# BACK-LIGHT-II.net
KiCad netlist of a schematic drawn in Altium Designer
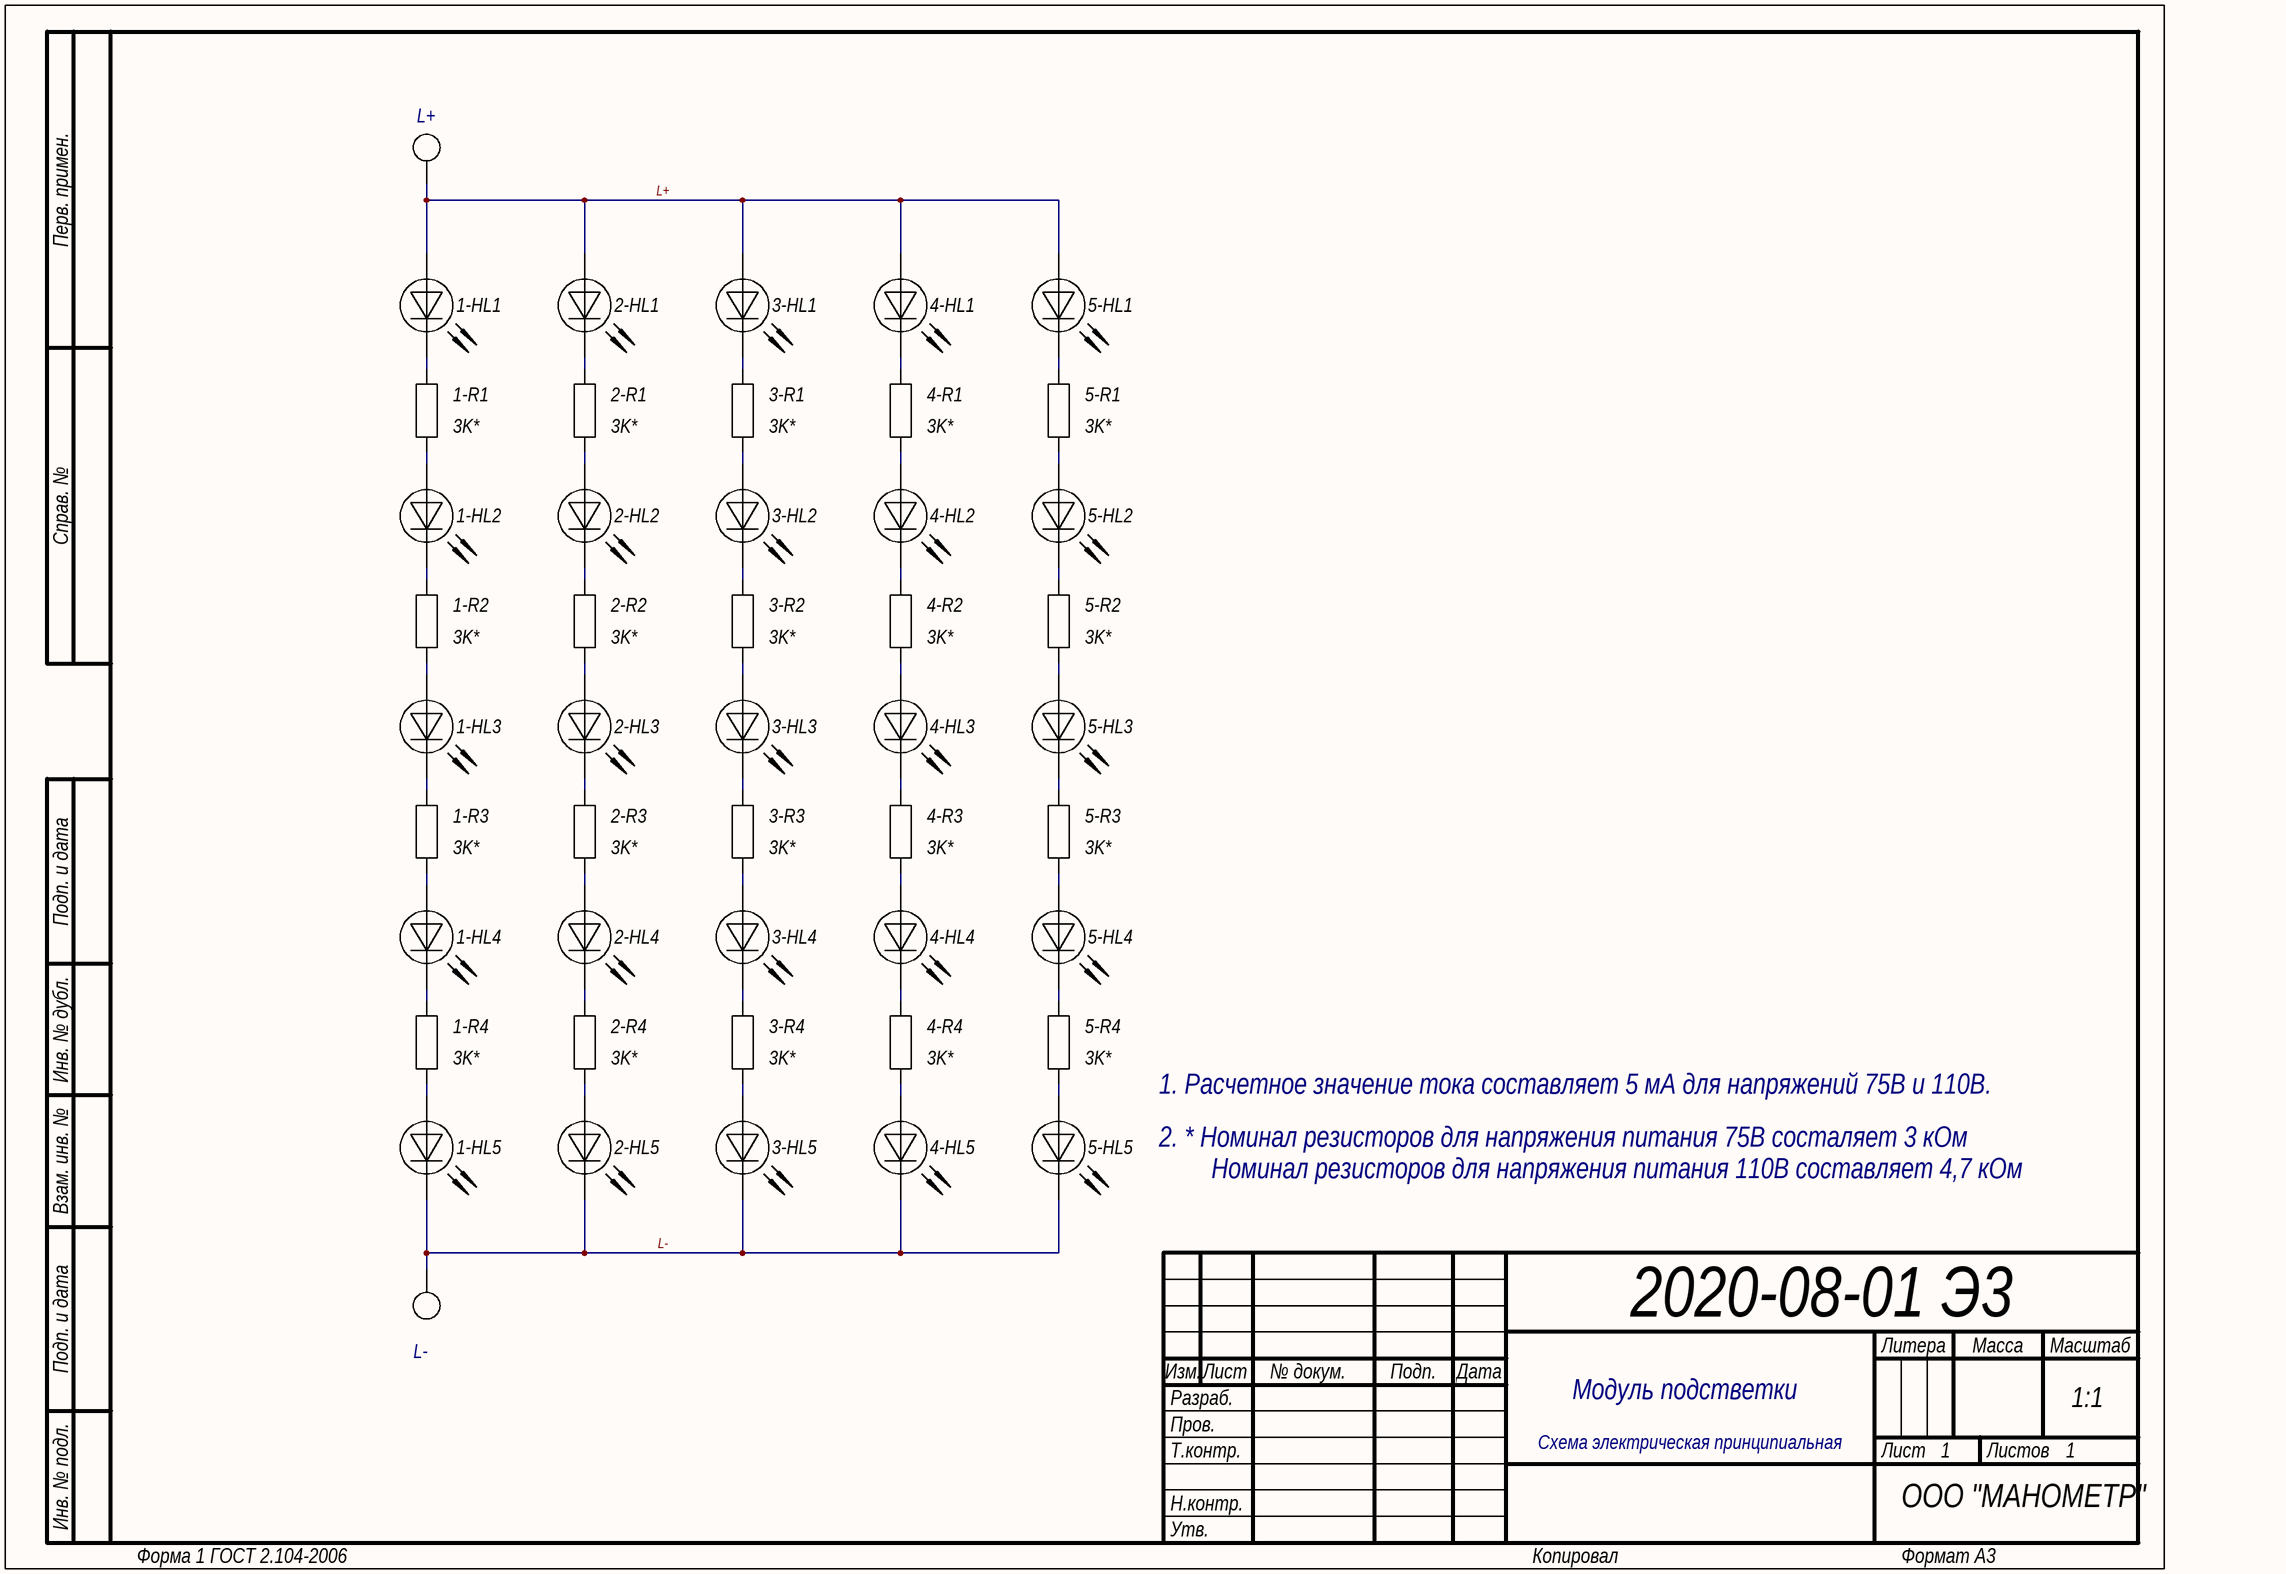
[diagram p0: BACK-LIGHT-II.SchDoc]

(export (version "E")
  (design (tool "Eeschema 10.0.6"))
  (components
    (comp (ref "1-HL1")
      (value "FYLS-1206UWC")
      (footprint "LED 1206")
      (description "Светодиод")
      (fields (field (name "TOLERANCE") "3K*"))
      (libsource (lib "MAXX") (part "LED"))
    )
    (comp (ref "1-HL2")
      (value "FYLS-1206UWC")
      (footprint "LED 1206")
      (description "Светодиод")
      (fields (field (name "TOLERANCE") "3K*"))
      (libsource (lib "MAXX") (part "LED"))
    )
    (comp (ref "1-HL3")
      (value "FYLS-1206UWC")
      (footprint "LED 1206")
      (description "Светодиод")
      (fields (field (name "TOLERANCE") "3K*"))
      (libsource (lib "MAXX") (part "LED"))
    )
    (comp (ref "1-HL4")
      (value "FYLS-1206UWC")
      (footprint "LED 1206")
      (description "Светодиод")
      (fields (field (name "TOLERANCE") "3K*"))
      (libsource (lib "MAXX") (part "LED"))
    )
    (comp (ref "1-HL5")
      (value "FYLS-1206UWC")
      (footprint "LED 1206")
      (description "Светодиод")
      (fields (field (name "TOLERANCE") "3K*"))
      (libsource (lib "MAXX") (part "LED"))
    )
    (comp (ref "1-R1")
      (value "3K*")
      (footprint "RC1206")
      (description "Постоянный углеродистый резистор")
      (libsource (lib "MAXX") (part "RES"))
    )
    (comp (ref "1-R2")
      (value "3K*")
      (footprint "RC1206")
      (description "Постоянный углеродистый резистор")
      (libsource (lib "MAXX") (part "RES"))
    )
    (comp (ref "1-R3")
      (value "3K*")
      (footprint "RC1206")
      (description "Постоянный углеродистый резистор")
      (libsource (lib "MAXX") (part "RES"))
    )
    (comp (ref "1-R4")
      (value "3K*")
      (footprint "RC1206")
      (description "Постоянный углеродистый резистор")
      (libsource (lib "MAXX") (part "RES"))
    )
    (comp (ref "2-HL1")
      (value "FYLS-1206UWC")
      (footprint "LED 1206")
      (description "Светодиод")
      (fields (field (name "TOLERANCE") "3K*"))
      (libsource (lib "MAXX") (part "LED"))
    )
    (comp (ref "2-HL2")
      (value "FYLS-1206UWC")
      (footprint "LED 1206")
      (description "Светодиод")
      (fields (field (name "TOLERANCE") "3K*"))
      (libsource (lib "MAXX") (part "LED"))
    )
    (comp (ref "2-HL3")
      (value "FYLS-1206UWC")
      (footprint "LED 1206")
      (description "Светодиод")
      (fields (field (name "TOLERANCE") "3K*"))
      (libsource (lib "MAXX") (part "LED"))
    )
    (comp (ref "2-HL4")
      (value "FYLS-1206UWC")
      (footprint "LED 1206")
      (description "Светодиод")
      (fields (field (name "TOLERANCE") "3K*"))
      (libsource (lib "MAXX") (part "LED"))
    )
    (comp (ref "2-HL5")
      (value "FYLS-1206UWC")
      (footprint "LED 1206")
      (description "Светодиод")
      (fields (field (name "TOLERANCE") "3K*"))
      (libsource (lib "MAXX") (part "LED"))
    )
    (comp (ref "2-R1")
      (value "3K*")
      (footprint "RC1206")
      (description "Постоянный углеродистый резистор")
      (libsource (lib "MAXX") (part "RES"))
    )
    (comp (ref "2-R2")
      (value "3K*")
      (footprint "RC1206")
      (description "Постоянный углеродистый резистор")
      (libsource (lib "MAXX") (part "RES"))
    )
    (comp (ref "2-R3")
      (value "3K*")
      (footprint "RC1206")
      (description "Постоянный углеродистый резистор")
      (libsource (lib "MAXX") (part "RES"))
    )
    (comp (ref "2-R4")
      (value "3K*")
      (footprint "RC1206")
      (description "Постоянный углеродистый резистор")
      (libsource (lib "MAXX") (part "RES"))
    )
    (comp (ref "3-HL1")
      (value "FYLS-1206UWC")
      (footprint "LED 1206")
      (description "Светодиод")
      (fields (field (name "TOLERANCE") "3K*"))
      (libsource (lib "MAXX") (part "LED"))
    )
    (comp (ref "3-HL2")
      (value "FYLS-1206UWC")
      (footprint "LED 1206")
      (description "Светодиод")
      (fields (field (name "TOLERANCE") "3K*"))
      (libsource (lib "MAXX") (part "LED"))
    )
    (comp (ref "3-HL3")
      (value "FYLS-1206UWC")
      (footprint "LED 1206")
      (description "Светодиод")
      (fields (field (name "TOLERANCE") "3K*"))
      (libsource (lib "MAXX") (part "LED"))
    )
    (comp (ref "3-HL4")
      (value "FYLS-1206UWC")
      (footprint "LED 1206")
      (description "Светодиод")
      (fields (field (name "TOLERANCE") "3K*"))
      (libsource (lib "MAXX") (part "LED"))
    )
    (comp (ref "3-HL5")
      (value "FYLS-1206UWC")
      (footprint "LED 1206")
      (description "Светодиод")
      (fields (field (name "TOLERANCE") "3K*"))
      (libsource (lib "MAXX") (part "LED"))
    )
    (comp (ref "3-R1")
      (value "3K*")
      (footprint "RC1206")
      (description "Постоянный углеродистый резистор")
      (libsource (lib "MAXX") (part "RES"))
    )
    (comp (ref "3-R2")
      (value "3K*")
      (footprint "RC1206")
      (description "Постоянный углеродистый резистор")
      (libsource (lib "MAXX") (part "RES"))
    )
    (comp (ref "3-R3")
      (value "3K*")
      (footprint "RC1206")
      (description "Постоянный углеродистый резистор")
      (libsource (lib "MAXX") (part "RES"))
    )
    (comp (ref "3-R4")
      (value "3K*")
      (footprint "RC1206")
      (description "Постоянный углеродистый резистор")
      (libsource (lib "MAXX") (part "RES"))
    )
    (comp (ref "4-HL1")
      (value "FYLS-1206UWC")
      (footprint "LED 1206")
      (description "Светодиод")
      (fields (field (name "TOLERANCE") "3K*"))
      (libsource (lib "MAXX") (part "LED"))
    )
    (comp (ref "4-HL2")
      (value "FYLS-1206UWC")
      (footprint "LED 1206")
      (description "Светодиод")
      (fields (field (name "TOLERANCE") "3K*"))
      (libsource (lib "MAXX") (part "LED"))
    )
    (comp (ref "4-HL3")
      (value "FYLS-1206UWC")
      (footprint "LED 1206")
      (description "Светодиод")
      (fields (field (name "TOLERANCE") "3K*"))
      (libsource (lib "MAXX") (part "LED"))
    )
    (comp (ref "4-HL4")
      (value "FYLS-1206UWC")
      (footprint "LED 1206")
      (description "Светодиод")
      (fields (field (name "TOLERANCE") "3K*"))
      (libsource (lib "MAXX") (part "LED"))
    )
    (comp (ref "4-HL5")
      (value "FYLS-1206UWC")
      (footprint "LED 1206")
      (description "Светодиод")
      (fields (field (name "TOLERANCE") "3K*"))
      (libsource (lib "MAXX") (part "LED"))
    )
    (comp (ref "4-R1")
      (value "3K*")
      (footprint "RC1206")
      (description "Постоянный углеродистый резистор")
      (libsource (lib "MAXX") (part "RES"))
    )
    (comp (ref "4-R2")
      (value "3K*")
      (footprint "RC1206")
      (description "Постоянный углеродистый резистор")
      (libsource (lib "MAXX") (part "RES"))
    )
    (comp (ref "4-R3")
      (value "3K*")
      (footprint "RC1206")
      (description "Постоянный углеродистый резистор")
      (libsource (lib "MAXX") (part "RES"))
    )
    (comp (ref "4-R4")
      (value "3K*")
      (footprint "RC1206")
      (description "Постоянный углеродистый резистор")
      (libsource (lib "MAXX") (part "RES"))
    )
    (comp (ref "5-HL1")
      (value "FYLS-1206UWC")
      (footprint "LED 1206")
      (description "Светодиод")
      (fields (field (name "TOLERANCE") "3K*"))
      (libsource (lib "MAXX") (part "LED"))
    )
    (comp (ref "5-HL2")
      (value "FYLS-1206UWC")
      (footprint "LED 1206")
      (description "Светодиод")
      (fields (field (name "TOLERANCE") "3K*"))
      (libsource (lib "MAXX") (part "LED"))
    )
    (comp (ref "5-HL3")
      (value "FYLS-1206UWC")
      (footprint "LED 1206")
      (description "Светодиод")
      (fields (field (name "TOLERANCE") "3K*"))
      (libsource (lib "MAXX") (part "LED"))
    )
    (comp (ref "5-HL4")
      (value "FYLS-1206UWC")
      (footprint "LED 1206")
      (description "Светодиод")
      (fields (field (name "TOLERANCE") "3K*"))
      (libsource (lib "MAXX") (part "LED"))
    )
    (comp (ref "5-HL5")
      (value "FYLS-1206UWC")
      (footprint "LED 1206")
      (description "Светодиод")
      (fields (field (name "TOLERANCE") "3K*"))
      (libsource (lib "MAXX") (part "LED"))
    )
    (comp (ref "5-R1")
      (value "3K*")
      (footprint "RC1206")
      (description "Постоянный углеродистый резистор")
      (libsource (lib "MAXX") (part "RES"))
    )
    (comp (ref "5-R2")
      (value "3K*")
      (footprint "RC1206")
      (description "Постоянный углеродистый резистор")
      (libsource (lib "MAXX") (part "RES"))
    )
    (comp (ref "5-R3")
      (value "3K*")
      (footprint "RC1206")
      (description "Постоянный углеродистый резистор")
      (libsource (lib "MAXX") (part "RES"))
    )
    (comp (ref "5-R4")
      (value "3K*")
      (footprint "RC1206")
      (description "Постоянный углеродистый резистор")
      (libsource (lib "MAXX") (part "RES"))
    )
    (comp (ref "L+") (value "~") (footprint "PIN") (libsource (lib "MAXX") (part "PIN")))
    (comp (ref "L-") (value "~") (footprint "PIN") (libsource (lib "MAXX") (part "PIN")))
  )
  (nets
    (net (code "1") (name "/L+") (class "Default")
      (node (ref "1-HL1") (pin "1") (pinfunction "A_1") (pintype "passive"))
      (node (ref "2-HL1") (pin "1") (pinfunction "A_1") (pintype "passive"))
      (node (ref "3-HL1") (pin "1") (pinfunction "A_1") (pintype "passive"))
      (node (ref "4-HL1") (pin "1") (pinfunction "A_1") (pintype "passive"))
      (node (ref "5-HL1") (pin "1") (pinfunction "A_1") (pintype "passive"))
      (node (ref "L+") (pin "PIN") (pinfunction "PIN_PIN") (pintype "passive"))
    )
    (net (code "2") (name "/L-") (class "Default")
      (node (ref "1-HL5") (pin "2") (pinfunction "K_2") (pintype "passive"))
      (node (ref "2-HL5") (pin "2") (pinfunction "K_2") (pintype "passive"))
      (node (ref "3-HL5") (pin "2") (pinfunction "K_2") (pintype "passive"))
      (node (ref "4-HL5") (pin "2") (pinfunction "K_2") (pintype "passive"))
      (node (ref "5-HL5") (pin "2") (pinfunction "K_2") (pintype "passive"))
      (node (ref "L-") (pin "PIN") (pinfunction "PIN_PIN") (pintype "passive"))
    )
    (net (code "3") (name "Net-(1-HL1-K)") (class "Default")
      (node (ref "1-HL1") (pin "2") (pinfunction "K_2") (pintype "passive"))
      (node (ref "1-R1") (pin "1") (pinfunction "1_1") (pintype "passive"))
    )
    (net (code "4") (name "Net-(1-HL2-A)") (class "Default")
      (node (ref "1-HL2") (pin "1") (pinfunction "A_1") (pintype "passive"))
      (node (ref "1-R1") (pin "2") (pinfunction "2_2") (pintype "passive"))
    )
    (net (code "5") (name "Net-(1-HL2-K)") (class "Default")
      (node (ref "1-HL2") (pin "2") (pinfunction "K_2") (pintype "passive"))
      (node (ref "1-R2") (pin "1") (pinfunction "1_1") (pintype "passive"))
    )
    (net (code "6") (name "Net-(1-HL3-A)") (class "Default")
      (node (ref "1-HL3") (pin "1") (pinfunction "A_1") (pintype "passive"))
      (node (ref "1-R2") (pin "2") (pinfunction "2_2") (pintype "passive"))
    )
    (net (code "7") (name "Net-(1-HL3-K)") (class "Default")
      (node (ref "1-HL3") (pin "2") (pinfunction "K_2") (pintype "passive"))
      (node (ref "1-R3") (pin "1") (pinfunction "1_1") (pintype "passive"))
    )
    (net (code "8") (name "Net-(1-HL4-A)") (class "Default")
      (node (ref "1-HL4") (pin "1") (pinfunction "A_1") (pintype "passive"))
      (node (ref "1-R3") (pin "2") (pinfunction "2_2") (pintype "passive"))
    )
    (net (code "9") (name "Net-(1-HL4-K)") (class "Default")
      (node (ref "1-HL4") (pin "2") (pinfunction "K_2") (pintype "passive"))
      (node (ref "1-R4") (pin "1") (pinfunction "1_1") (pintype "passive"))
    )
    (net (code "10") (name "Net-(1-HL5-A)") (class "Default")
      (node (ref "1-HL5") (pin "1") (pinfunction "A_1") (pintype "passive"))
      (node (ref "1-R4") (pin "2") (pinfunction "2_2") (pintype "passive"))
    )
    (net (code "11") (name "Net-(2-HL1-K)") (class "Default")
      (node (ref "2-HL1") (pin "2") (pinfunction "K_2") (pintype "passive"))
      (node (ref "2-R1") (pin "1") (pinfunction "1_1") (pintype "passive"))
    )
    (net (code "12") (name "Net-(2-HL2-A)") (class "Default")
      (node (ref "2-HL2") (pin "1") (pinfunction "A_1") (pintype "passive"))
      (node (ref "2-R1") (pin "2") (pinfunction "2_2") (pintype "passive"))
    )
    (net (code "13") (name "Net-(2-HL2-K)") (class "Default")
      (node (ref "2-HL2") (pin "2") (pinfunction "K_2") (pintype "passive"))
      (node (ref "2-R2") (pin "1") (pinfunction "1_1") (pintype "passive"))
    )
    (net (code "14") (name "Net-(2-HL3-A)") (class "Default")
      (node (ref "2-HL3") (pin "1") (pinfunction "A_1") (pintype "passive"))
      (node (ref "2-R2") (pin "2") (pinfunction "2_2") (pintype "passive"))
    )
    (net (code "15") (name "Net-(2-HL3-K)") (class "Default")
      (node (ref "2-HL3") (pin "2") (pinfunction "K_2") (pintype "passive"))
      (node (ref "2-R3") (pin "1") (pinfunction "1_1") (pintype "passive"))
    )
    (net (code "16") (name "Net-(2-HL4-A)") (class "Default")
      (node (ref "2-HL4") (pin "1") (pinfunction "A_1") (pintype "passive"))
      (node (ref "2-R3") (pin "2") (pinfunction "2_2") (pintype "passive"))
    )
    (net (code "17") (name "Net-(2-HL4-K)") (class "Default")
      (node (ref "2-HL4") (pin "2") (pinfunction "K_2") (pintype "passive"))
      (node (ref "2-R4") (pin "1") (pinfunction "1_1") (pintype "passive"))
    )
    (net (code "18") (name "Net-(2-HL5-A)") (class "Default")
      (node (ref "2-HL5") (pin "1") (pinfunction "A_1") (pintype "passive"))
      (node (ref "2-R4") (pin "2") (pinfunction "2_2") (pintype "passive"))
    )
    (net (code "19") (name "Net-(3-HL1-K)") (class "Default")
      (node (ref "3-HL1") (pin "2") (pinfunction "K_2") (pintype "passive"))
      (node (ref "3-R1") (pin "1") (pinfunction "1_1") (pintype "passive"))
    )
    (net (code "20") (name "Net-(3-HL2-A)") (class "Default")
      (node (ref "3-HL2") (pin "1") (pinfunction "A_1") (pintype "passive"))
      (node (ref "3-R1") (pin "2") (pinfunction "2_2") (pintype "passive"))
    )
    (net (code "21") (name "Net-(3-HL2-K)") (class "Default")
      (node (ref "3-HL2") (pin "2") (pinfunction "K_2") (pintype "passive"))
      (node (ref "3-R2") (pin "1") (pinfunction "1_1") (pintype "passive"))
    )
    (net (code "22") (name "Net-(3-HL3-A)") (class "Default")
      (node (ref "3-HL3") (pin "1") (pinfunction "A_1") (pintype "passive"))
      (node (ref "3-R2") (pin "2") (pinfunction "2_2") (pintype "passive"))
    )
    (net (code "23") (name "Net-(3-HL3-K)") (class "Default")
      (node (ref "3-HL3") (pin "2") (pinfunction "K_2") (pintype "passive"))
      (node (ref "3-R3") (pin "1") (pinfunction "1_1") (pintype "passive"))
    )
    (net (code "24") (name "Net-(3-HL4-A)") (class "Default")
      (node (ref "3-HL4") (pin "1") (pinfunction "A_1") (pintype "passive"))
      (node (ref "3-R3") (pin "2") (pinfunction "2_2") (pintype "passive"))
    )
    (net (code "25") (name "Net-(3-HL4-K)") (class "Default")
      (node (ref "3-HL4") (pin "2") (pinfunction "K_2") (pintype "passive"))
      (node (ref "3-R4") (pin "1") (pinfunction "1_1") (pintype "passive"))
    )
    (net (code "26") (name "Net-(3-HL5-A)") (class "Default")
      (node (ref "3-HL5") (pin "1") (pinfunction "A_1") (pintype "passive"))
      (node (ref "3-R4") (pin "2") (pinfunction "2_2") (pintype "passive"))
    )
    (net (code "27") (name "Net-(4-HL1-K)") (class "Default")
      (node (ref "4-HL1") (pin "2") (pinfunction "K_2") (pintype "passive"))
      (node (ref "4-R1") (pin "1") (pinfunction "1_1") (pintype "passive"))
    )
    (net (code "28") (name "Net-(4-HL2-A)") (class "Default")
      (node (ref "4-HL2") (pin "1") (pinfunction "A_1") (pintype "passive"))
      (node (ref "4-R1") (pin "2") (pinfunction "2_2") (pintype "passive"))
    )
    (net (code "29") (name "Net-(4-HL2-K)") (class "Default")
      (node (ref "4-HL2") (pin "2") (pinfunction "K_2") (pintype "passive"))
      (node (ref "4-R2") (pin "1") (pinfunction "1_1") (pintype "passive"))
    )
    (net (code "30") (name "Net-(4-HL3-A)") (class "Default")
      (node (ref "4-HL3") (pin "1") (pinfunction "A_1") (pintype "passive"))
      (node (ref "4-R2") (pin "2") (pinfunction "2_2") (pintype "passive"))
    )
    (net (code "31") (name "Net-(4-HL3-K)") (class "Default")
      (node (ref "4-HL3") (pin "2") (pinfunction "K_2") (pintype "passive"))
      (node (ref "4-R3") (pin "1") (pinfunction "1_1") (pintype "passive"))
    )
    (net (code "32") (name "Net-(4-HL4-A)") (class "Default")
      (node (ref "4-HL4") (pin "1") (pinfunction "A_1") (pintype "passive"))
      (node (ref "4-R3") (pin "2") (pinfunction "2_2") (pintype "passive"))
    )
    (net (code "33") (name "Net-(4-HL4-K)") (class "Default")
      (node (ref "4-HL4") (pin "2") (pinfunction "K_2") (pintype "passive"))
      (node (ref "4-R4") (pin "1") (pinfunction "1_1") (pintype "passive"))
    )
    (net (code "34") (name "Net-(4-HL5-A)") (class "Default")
      (node (ref "4-HL5") (pin "1") (pinfunction "A_1") (pintype "passive"))
      (node (ref "4-R4") (pin "2") (pinfunction "2_2") (pintype "passive"))
    )
    (net (code "35") (name "Net-(5-HL1-K)") (class "Default")
      (node (ref "5-HL1") (pin "2") (pinfunction "K_2") (pintype "passive"))
      (node (ref "5-R1") (pin "1") (pinfunction "1_1") (pintype "passive"))
    )
    (net (code "36") (name "Net-(5-HL2-A)") (class "Default")
      (node (ref "5-HL2") (pin "1") (pinfunction "A_1") (pintype "passive"))
      (node (ref "5-R1") (pin "2") (pinfunction "2_2") (pintype "passive"))
    )
    (net (code "37") (name "Net-(5-HL2-K)") (class "Default")
      (node (ref "5-HL2") (pin "2") (pinfunction "K_2") (pintype "passive"))
      (node (ref "5-R2") (pin "1") (pinfunction "1_1") (pintype "passive"))
    )
    (net (code "38") (name "Net-(5-HL3-A)") (class "Default")
      (node (ref "5-HL3") (pin "1") (pinfunction "A_1") (pintype "passive"))
      (node (ref "5-R2") (pin "2") (pinfunction "2_2") (pintype "passive"))
    )
    (net (code "39") (name "Net-(5-HL3-K)") (class "Default")
      (node (ref "5-HL3") (pin "2") (pinfunction "K_2") (pintype "passive"))
      (node (ref "5-R3") (pin "1") (pinfunction "1_1") (pintype "passive"))
    )
    (net (code "40") (name "Net-(5-HL4-A)") (class "Default")
      (node (ref "5-HL4") (pin "1") (pinfunction "A_1") (pintype "passive"))
      (node (ref "5-R3") (pin "2") (pinfunction "2_2") (pintype "passive"))
    )
    (net (code "41") (name "Net-(5-HL4-K)") (class "Default")
      (node (ref "5-HL4") (pin "2") (pinfunction "K_2") (pintype "passive"))
      (node (ref "5-R4") (pin "1") (pinfunction "1_1") (pintype "passive"))
    )
    (net (code "42") (name "Net-(5-HL5-A)") (class "Default")
      (node (ref "5-HL5") (pin "1") (pinfunction "A_1") (pintype "passive"))
      (node (ref "5-R4") (pin "2") (pinfunction "2_2") (pintype "passive"))
    )
  )
)
